# POWER.net
KiCad netlist of a schematic drawn in Altium Designer
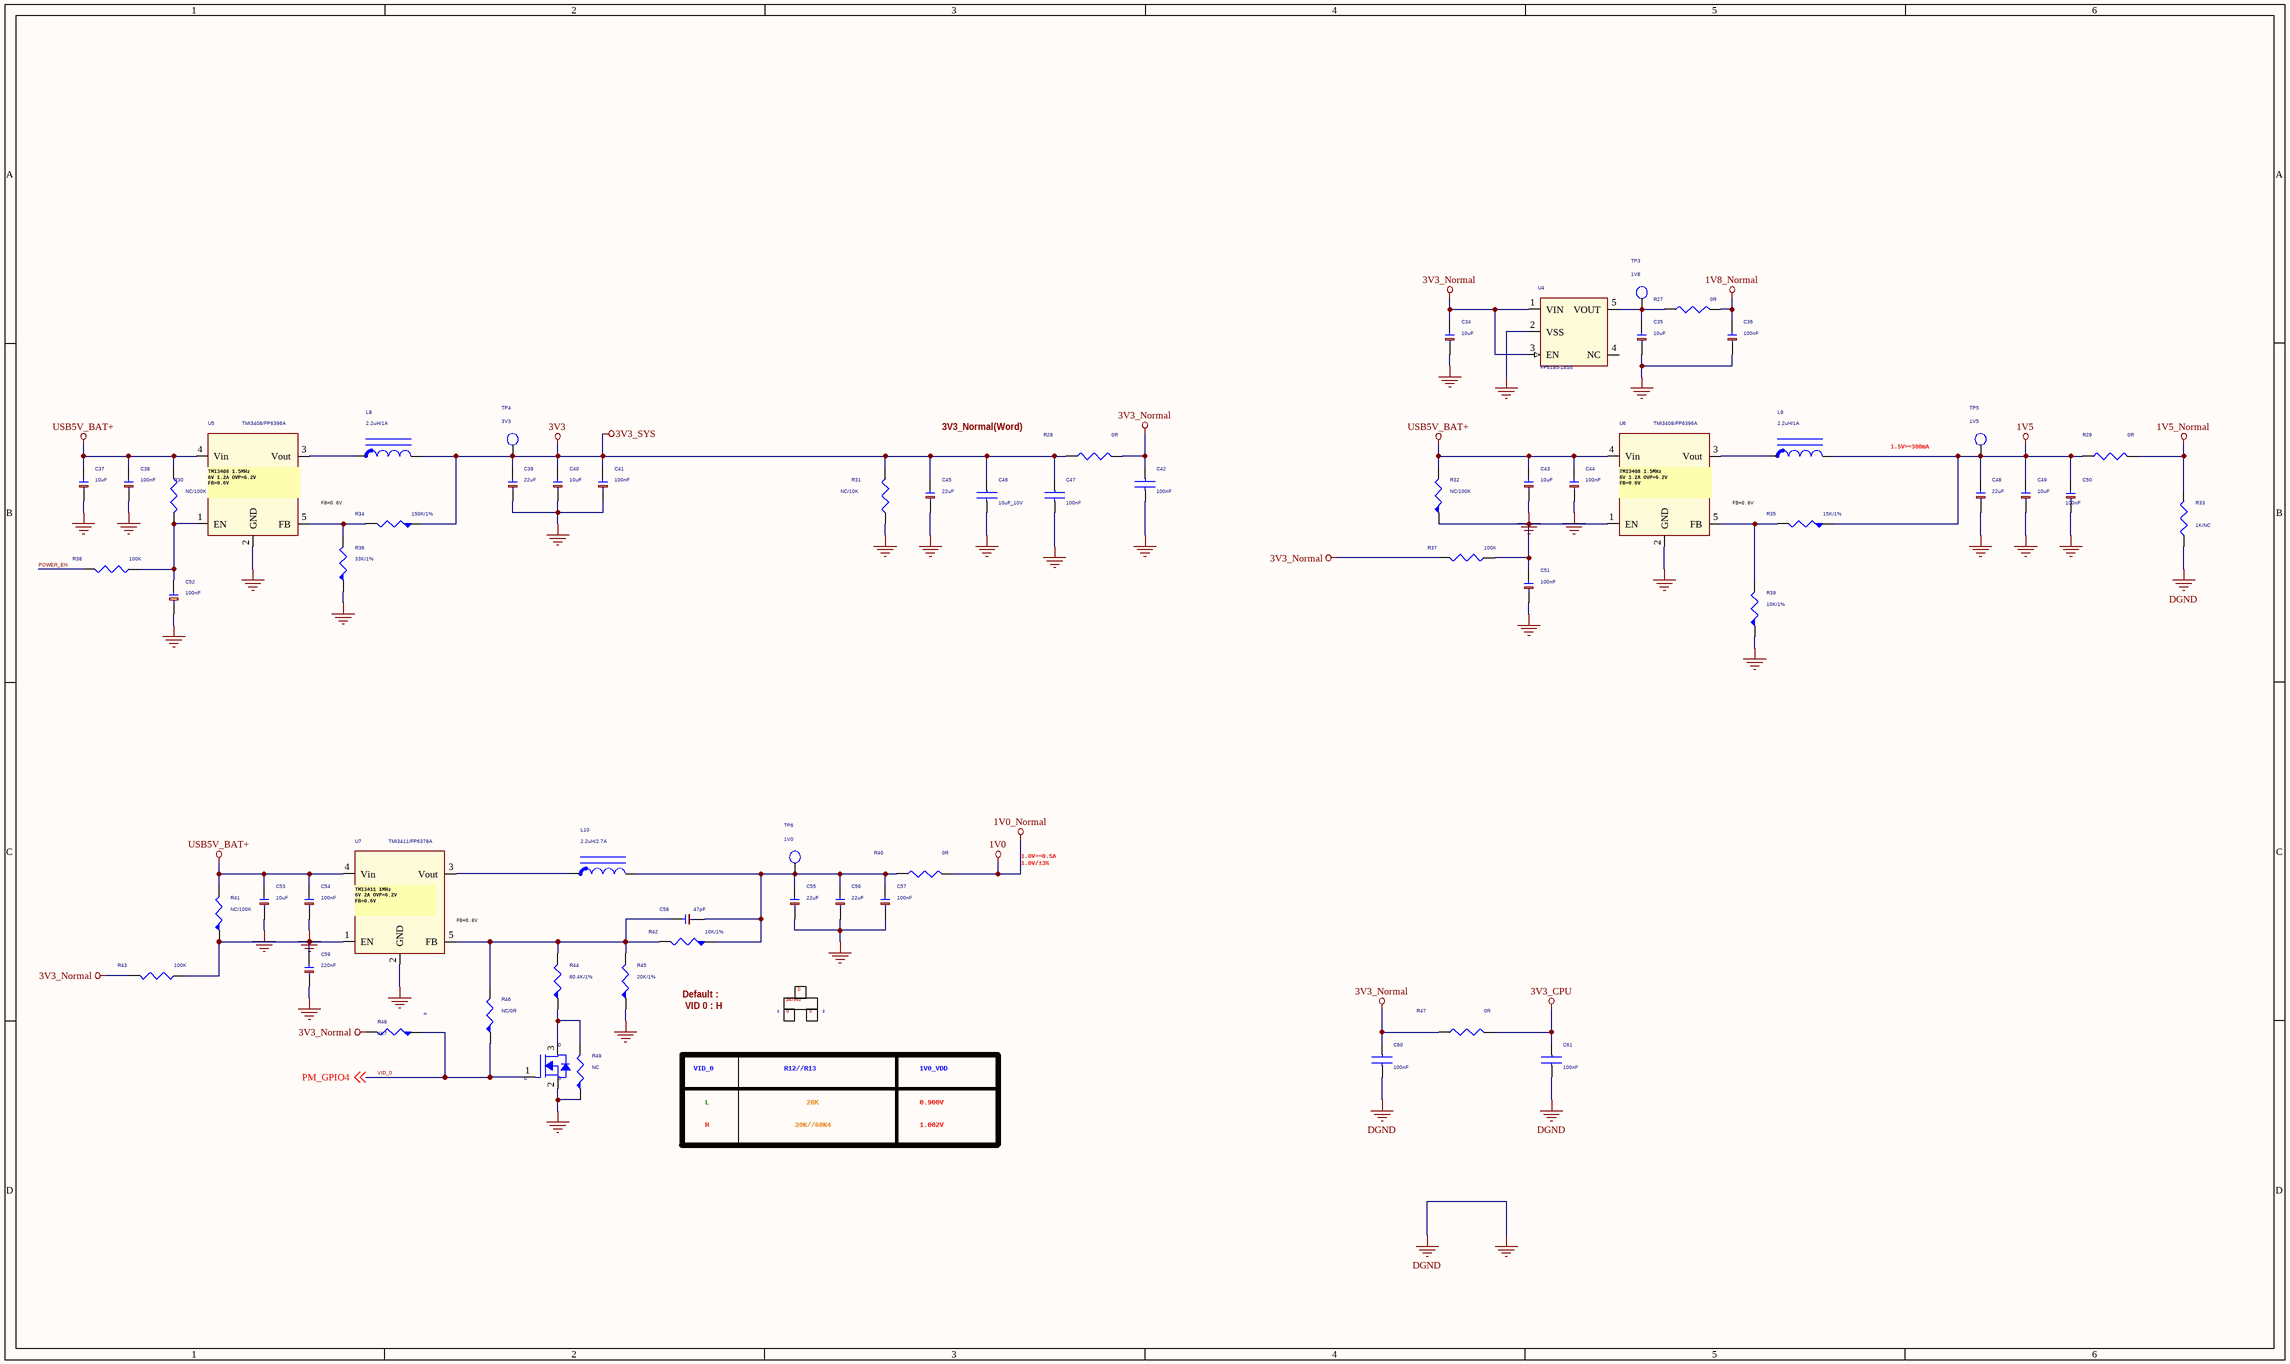
[diagram p0: POWER.SchDoc]

(export (version "E")
  (design (tool "Eeschema 10.0.6"))
  (components
    (comp (ref "C34")
      (value "10uF")
      (footprint "C0402")
      (description "[ 100nF(0.1uF),10V,X7R ](0402)")
      (fields (field (name "CREATOR") "Alan.Liu#6135/0920796617"))
      (libsource (lib "*") (part "C0402/100nF/10V/X7R"))
    )
    (comp (ref "C35")
      (value "10uF")
      (footprint "C0402")
      (description "[ 100nF(0.1uF),10V,X7R ](0402)")
      (fields (field (name "CREATOR") "Alan.Liu#6135/0920796617"))
      (libsource (lib "*") (part "C0402/100nF/10V/X7R"))
    )
    (comp (ref "C36")
      (value "100nF")
      (footprint "C0402")
      (description "[ 100nF(0.1uF),10V,X7R ](0402)")
      (fields (field (name "CREATOR") "Alan.Liu#6135/0920796617"))
      (libsource (lib "*") (part "C0402/100nF/10V/X7R"))
    )
    (comp (ref "C37")
      (value "10uF")
      (footprint "C0402")
      (description "[ 100nF(0.1uF),10V,X7R ](0402)")
      (fields (field (name "CREATOR") "Alan.Liu#6135/0920796617"))
      (libsource (lib "*") (part "C0402/100nF/10V/X7R"))
    )
    (comp (ref "C38")
      (value "100nF")
      (footprint "C0402")
      (description "[ 100nF(0.1uF),10V,X7R ](0402)")
      (fields (field (name "CREATOR") "Alan.Liu#6135/0920796617"))
      (libsource (lib "*") (part "C0402/100nF/10V/X7R"))
    )
    (comp (ref "C39")
      (value "22uF")
      (footprint "C0402")
      (description "[ 100nF(0.1uF),10V,X7R ](0402)")
      (fields (field (name "CREATOR") "Alan.Liu#6135/0920796617"))
      (libsource (lib "*") (part "C0402/100nF/10V/X7R"))
    )
    (comp (ref "C40")
      (value "10uF")
      (footprint "C0402")
      (description "[ 100nF(0.1uF),10V,X7R ](0402)")
      (fields (field (name "CREATOR") "Alan.Liu#6135/0920796617"))
      (libsource (lib "*") (part "C0402/100nF/10V/X7R"))
    )
    (comp (ref "C41")
      (value "100nF")
      (footprint "C0402")
      (description "[ 100nF(0.1uF),10V,X7R ](0402)")
      (fields (field (name "CREATOR") "Alan.Liu#6135/0920796617"))
      (libsource (lib "*") (part "C0402/100nF/10V/X7R"))
    )
    (comp (ref "C42") (value "100nF") (footprint "C0402") (libsource (lib "*") (part "CAP NP2")))
    (comp (ref "C43")
      (value "10uF")
      (footprint "C0402")
      (description "[ 100nF(0.1uF),10V,X7R ](0402)")
      (fields (field (name "CREATOR") "Alan.Liu#6135/0920796617"))
      (libsource (lib "*") (part "C0402/100nF/10V/X7R"))
    )
    (comp (ref "C44")
      (value "100nF")
      (footprint "C0402")
      (description "[ 100nF(0.1uF),10V,X7R ](0402)")
      (fields (field (name "CREATOR") "Alan.Liu#6135/0920796617"))
      (libsource (lib "*") (part "C0402/100nF/10V/X7R"))
    )
    (comp (ref "C45")
      (value "22uF")
      (footprint "C0402")
      (description "[ 100nF(0.1uF),10V,X7R ](0402)")
      (fields (field (name "CREATOR") "Alan.Liu#6135/0920796617"))
      (libsource (lib "*") (part "C0402/100nF/10V/X7R"))
    )
    (comp (ref "C46") (value "10uF_10V") (footprint "C0603") (libsource (lib "*") (part "CAP NP2")))
    (comp (ref "C47") (value "100nF") (footprint "C0402") (libsource (lib "*") (part "CAP NP2")))
    (comp (ref "C48")
      (value "22uF")
      (footprint "C0402")
      (description "[ 100nF(0.1uF),10V,X7R ](0402)")
      (fields (field (name "CREATOR") "Alan.Liu#6135/0920796617"))
      (libsource (lib "*") (part "C0402/100nF/10V/X7R"))
    )
    (comp (ref "C49")
      (value "10uF")
      (footprint "C0402")
      (description "[ 100nF(0.1uF),10V,X7R ](0402)")
      (fields (field (name "CREATOR") "Alan.Liu#6135/0920796617"))
      (libsource (lib "*") (part "C0402/100nF/10V/X7R"))
    )
    (comp (ref "C50") (value "100nF") (footprint "C0402") (libsource (lib "*") (part "C0805_10uF")))
    (comp (ref "C51")
      (value "100nF")
      (footprint "C0402")
      (description "[ 100nF(0.1uF),10V,X7R ](0402)")
      (fields (field (name "CREATOR") "Alan.Liu#6135/0920796617"))
      (libsource (lib "*") (part "C0402/100nF/10V/X7R"))
    )
    (comp (ref "C52")
      (value "100nF")
      (footprint "C0402")
      (description "[ 100nF(0.1uF),10V,X7R ](0402)")
      (fields (field (name "CREATOR") "Alan.Liu#6135/0920796617"))
      (libsource (lib "*") (part "C0402/100nF/10V/X7R"))
    )
    (comp (ref "C53")
      (value "10uF")
      (footprint "C0402")
      (description "[ 100nF(0.1uF),10V,X7R ](0402)")
      (fields (field (name "CREATOR") "Alan.Liu#6135/0920796617"))
      (libsource (lib "*") (part "C0402/100nF/10V/X7R"))
    )
    (comp (ref "C54")
      (value "100nF")
      (footprint "C0402")
      (description "[ 100nF(0.1uF),10V,X7R ](0402)")
      (fields (field (name "CREATOR") "Alan.Liu#6135/0920796617"))
      (libsource (lib "*") (part "C0402/100nF/10V/X7R"))
    )
    (comp (ref "C55")
      (value "22uF")
      (footprint "C0402")
      (description "[ 100nF(0.1uF),10V,X7R ](0402)")
      (fields (field (name "CREATOR") "Alan.Liu#6135/0920796617"))
      (libsource (lib "*") (part "C0402/100nF/10V/X7R"))
    )
    (comp (ref "C56")
      (value "22uF")
      (footprint "C0402")
      (description "[ 100nF(0.1uF),10V,X7R ](0402)")
      (fields (field (name "CREATOR") "Alan.Liu#6135/0920796617"))
      (libsource (lib "*") (part "C0402/100nF/10V/X7R"))
    )
    (comp (ref "C57")
      (value "100nF")
      (footprint "C0402")
      (description "[ 100nF(0.1uF),10V,X7R ](0402)")
      (fields (field (name "CREATOR") "Alan.Liu#6135/0920796617"))
      (libsource (lib "*") (part "C0402/100nF/10V/X7R"))
    )
    (comp (ref "C58")
      (value "47pF")
      (footprint "C0402")
      (description "[ 100nF(0.1uF),10V,X7R ](0402)")
      (fields (field (name "CREATOR") "Alan.Liu#6135/0920796617"))
      (libsource (lib "") (part "C0402/100nF/10V/X7R_1"))
    )
    (comp (ref "C59")
      (value "220nF")
      (footprint "C0402")
      (description "[ 100nF(0.1uF),10V,X7R ](0402)")
      (fields (field (name "CREATOR") "Alan.Liu#6135/0920796617"))
      (libsource (lib "*") (part "C0402/100nF/10V/X7R"))
    )
    (comp (ref "C60") (value "100nF") (footprint "C0402") (libsource (lib "*") (part "CAP NP2")))
    (comp (ref "C61") (value "100nF") (footprint "C0402") (libsource (lib "*") (part "CAP NP2")))
    (comp (ref "L8")
      (value "2.2uH/1A")
      (footprint "SWPA3015S")
      (fields (field (name "CREATOR") "Alan.Liu#6135/0920796617"))
      (libsource (lib "*") (part "CHOKE_4.7uH/4.1A-L8.0W8.0H4.0"))
    )
    (comp (ref "L9")
      (value "2.2uH/1A")
      (footprint "SWPA3015S")
      (fields (field (name "CREATOR") "Alan.Liu#6135/0920796617"))
      (libsource (lib "*") (part "CHOKE_4.7uH/4.1A-L8.0W8.0H4.0"))
    )
    (comp (ref "L10")
      (value "2.2uH/2.7A")
      (footprint "L-MLPS-4018")
      (fields (field (name "CREATOR") "Alan.Liu#6135/0920796617"))
      (libsource (lib "*") (part "CHOKE_4.7uH/4.1A-L8.0W8.0H4.0"))
    )
    (comp (ref "Q4") (value "2N7002") (footprint "SOT-23") (libsource (lib "*") (part "AO3400_SOT23")))
    (comp (ref "R27") (value "0R") (footprint "R0402") (libsource (lib "*") (part "R_Dup1")))
    (comp (ref "R28") (value "0R") (footprint "R1210") (libsource (lib "*") (part "R_Dup2")))
    (comp (ref "R29") (value "0R") (footprint "R1210") (libsource (lib "*") (part "R_Dup2")))
    (comp (ref "R30") (value "NC/100K") (footprint "R0402") (libsource (lib "*") (part "R_Dup2")))
    (comp (ref "R31") (value "NC/10K") (footprint "R0402") (libsource (lib "*") (part "R_Dup2")))
    (comp (ref "R32") (value "NC/100K") (footprint "R0402") (libsource (lib "*") (part "R-PIN-Mark")))
    (comp (ref "R33") (value "1K/NC") (footprint "R0402") (libsource (lib "*") (part "R_Dup2")))
    (comp (ref "R34") (value "150K/1%") (footprint "R0402") (libsource (lib "*") (part "R-PIN-Mark")))
    (comp (ref "R35") (value "15K/1%") (footprint "R0402") (libsource (lib "*") (part "R-PIN-Mark")))
    (comp (ref "R36") (value "33K/1%") (footprint "R0402") (libsource (lib "*") (part "R-PIN-Mark")))
    (comp (ref "R37") (value "100K") (footprint "R0402") (libsource (lib "*") (part "R_Dup2")))
    (comp (ref "R38") (value "100K") (footprint "R0402") (libsource (lib "*") (part "R_Dup2")))
    (comp (ref "R39") (value "10K/1%") (footprint "R0402") (libsource (lib "*") (part "R-PIN-Mark")))
    (comp (ref "R40") (value "0R") (footprint "R1210") (libsource (lib "*") (part "R_Dup2")))
    (comp (ref "R41") (value "NC/100K") (footprint "R0402") (libsource (lib "*") (part "R-PIN-Mark")))
    (comp (ref "R42") (value "10K/1%") (footprint "R0402") (libsource (lib "*") (part "R-PIN-Mark")))
    (comp (ref "R43") (value "100K") (footprint "R0402") (libsource (lib "*") (part "R_Dup2")))
    (comp (ref "R44") (value "60.4K/1%") (footprint "R0402") (libsource (lib "*") (part "R-PIN-Mark")))
    (comp (ref "R45") (value "20K/1%") (footprint "R0402") (libsource (lib "*") (part "R-PIN-Mark")))
    (comp (ref "R46") (value "NC/0R") (footprint "R0402") (libsource (lib "*") (part "R-PIN-Mark")))
    (comp (ref "R47") (value "0R") (footprint "R1210") (libsource (lib "*") (part "R_Dup2")))
    (comp (ref "R48") (value "4K7") (footprint "R0402") (libsource (lib "*") (part "R-PIN-Mark")))
    (comp (ref "R49") (value "NC") (footprint "R0402") (libsource (lib "*") (part "R-PIN-Mark")))
    (comp (ref "TP3") (value "1V8") (footprint "TP") (libsource (lib "*") (part "T POINT R")))
    (comp (ref "TP4") (value "3V3") (footprint "TP") (libsource (lib "*") (part "T POINT R")))
    (comp (ref "TP5") (value "1V5") (footprint "TP") (libsource (lib "*") (part "T POINT R")))
    (comp (ref "TP6") (value "1V0") (footprint "TP") (libsource (lib "*") (part "T POINT R")))
    (comp (ref "U4") (value "FP6185-18S5") (footprint "SOT23-5P") (libsource (lib "*") (part "ADP1610_7")))
    (comp (ref "U5")
      (value "TMI3408/FP6396A")
      (footprint "SOT-23-5")
      (description "iD9306-AD")
      (fields (field (name "PART NUMBER") "300035100G"))
      (libsource (lib "*") (part "LDO,iD9306-AD,300mA_3"))
    )
    (comp (ref "U6")
      (value "TMI3408/FP6396A")
      (footprint "SOT-23-5")
      (description "iD9306-AD")
      (fields (field (name "PART NUMBER") "300035100G"))
      (libsource (lib "*") (part "LDO,iD9306-AD,300mA_3"))
    )
    (comp (ref "U7")
      (value "TMI3411/FP6378A")
      (footprint "SOT-23-5")
      (description "iD9306-AD")
      (fields (field (name "PART NUMBER") "300035100G"))
      (libsource (lib "*") (part "LDO,iD9306-AD,300mA_4"))
    )
  )
  (nets
    (net (code "1") (name "/POWER_EN") (class "Default")
      (node (ref "R38") (pin "2") (pinfunction "2_2") (pintype "passive"))
    )
    (net (code "2") (name "1V0") (class "Default")
      (node (ref "R40") (pin "2") (pinfunction "2_2") (pintype "passive"))
    )
    (net (code "3") (name "1V5") (class "Default")
      (node (ref "C48") (pin "2") (pinfunction "2_2") (pintype "passive"))
      (node (ref "C49") (pin "2") (pinfunction "2_2") (pintype "passive"))
      (node (ref "C50") (pin "1") (pinfunction "1_1") (pintype "passive"))
      (node (ref "L9") (pin "2") (pinfunction "2_2") (pintype "passive"))
      (node (ref "R29") (pin "1") (pinfunction "1_1") (pintype "passive"))
      (node (ref "R35") (pin "1") (pinfunction "1_1") (pintype "passive"))
      (node (ref "TP5") (pin "1") (pinfunction "TP_1") (pintype "passive"))
    )
    (net (code "4") (name "1V5_Normal") (class "Default")
      (node (ref "R29") (pin "2") (pinfunction "2_2") (pintype "passive"))
      (node (ref "R33") (pin "1") (pinfunction "1_1") (pintype "passive"))
    )
    (net (code "5") (name "1V8_Normal") (class "Default")
      (node (ref "C36") (pin "2") (pinfunction "2_2") (pintype "passive"))
      (node (ref "R27") (pin "2") (pinfunction "2_2") (pintype "passive"))
    )
    (net (code "6") (name "3V3") (class "Default")
      (node (ref "C39") (pin "2") (pinfunction "2_2") (pintype "passive"))
      (node (ref "C40") (pin "2") (pinfunction "2_2") (pintype "passive"))
      (node (ref "C41") (pin "2") (pinfunction "2_2") (pintype "passive"))
      (node (ref "C45") (pin "2") (pinfunction "2_2") (pintype "passive"))
      (node (ref "C46") (pin "1") (pinfunction "1_1") (pintype "passive"))
      (node (ref "C47") (pin "1") (pinfunction "1_1") (pintype "passive"))
      (node (ref "L8") (pin "2") (pinfunction "2_2") (pintype "passive"))
      (node (ref "R28") (pin "1") (pinfunction "1_1") (pintype "passive"))
      (node (ref "R31") (pin "1") (pinfunction "1_1") (pintype "passive"))
      (node (ref "R34") (pin "1") (pinfunction "1_1") (pintype "passive"))
      (node (ref "TP4") (pin "1") (pinfunction "TP_1") (pintype "passive"))
    )
    (net (code "7") (name "3V3_CPU") (class "Default")
      (node (ref "C61") (pin "1") (pinfunction "1_1") (pintype "passive"))
      (node (ref "R47") (pin "2") (pinfunction "2_2") (pintype "passive"))
    )
    (net (code "8") (name "3V3_Normal") (class "Default")
      (node (ref "C34") (pin "2") (pinfunction "2_2") (pintype "passive"))
      (node (ref "C42") (pin "1") (pinfunction "1_1") (pintype "passive"))
      (node (ref "C60") (pin "1") (pinfunction "1_1") (pintype "passive"))
      (node (ref "R28") (pin "2") (pinfunction "2_2") (pintype "passive"))
      (node (ref "R37") (pin "2") (pinfunction "2_2") (pintype "passive"))
      (node (ref "R43") (pin "1") (pinfunction "1_1") (pintype "passive"))
      (node (ref "R47") (pin "1") (pinfunction "1_1") (pintype "passive"))
      (node (ref "R48") (pin "2") (pinfunction "2_2") (pintype "passive"))
      (node (ref "U4") (pin "1") (pinfunction "VIN_1") (pintype "power_in"))
      (node (ref "U4") (pin "3") (pinfunction "EN_3") (pintype "input"))
    )
    (net (code "9") (name "DGND") (class "Default")
      (node (ref "C34") (pin "1") (pinfunction "1_1") (pintype "passive"))
      (node (ref "C35") (pin "1") (pinfunction "1_1") (pintype "passive"))
      (node (ref "C36") (pin "1") (pinfunction "1_1") (pintype "passive"))
      (node (ref "C37") (pin "1") (pinfunction "1_1") (pintype "passive"))
      (node (ref "C38") (pin "1") (pinfunction "1_1") (pintype "passive"))
      (node (ref "C39") (pin "1") (pinfunction "1_1") (pintype "passive"))
      (node (ref "C40") (pin "1") (pinfunction "1_1") (pintype "passive"))
      (node (ref "C41") (pin "1") (pinfunction "1_1") (pintype "passive"))
      (node (ref "C42") (pin "2") (pinfunction "2_2") (pintype "passive"))
      (node (ref "C43") (pin "1") (pinfunction "1_1") (pintype "passive"))
      (node (ref "C44") (pin "1") (pinfunction "1_1") (pintype "passive"))
      (node (ref "C45") (pin "1") (pinfunction "1_1") (pintype "passive"))
      (node (ref "C46") (pin "2") (pinfunction "2_2") (pintype "passive"))
      (node (ref "C47") (pin "2") (pinfunction "2_2") (pintype "passive"))
      (node (ref "C48") (pin "1") (pinfunction "1_1") (pintype "passive"))
      (node (ref "C49") (pin "1") (pinfunction "1_1") (pintype "passive"))
      (node (ref "C50") (pin "2") (pinfunction "2_2") (pintype "passive"))
      (node (ref "C51") (pin "1") (pinfunction "1_1") (pintype "passive"))
      (node (ref "C52") (pin "1") (pinfunction "1_1") (pintype "passive"))
      (node (ref "C53") (pin "1") (pinfunction "1_1") (pintype "passive"))
      (node (ref "C54") (pin "1") (pinfunction "1_1") (pintype "passive"))
      (node (ref "C55") (pin "1") (pinfunction "1_1") (pintype "passive"))
      (node (ref "C56") (pin "1") (pinfunction "1_1") (pintype "passive"))
      (node (ref "C57") (pin "1") (pinfunction "1_1") (pintype "passive"))
      (node (ref "C59") (pin "1") (pinfunction "1_1") (pintype "passive"))
      (node (ref "C60") (pin "2") (pinfunction "2_2") (pintype "passive"))
      (node (ref "C61") (pin "2") (pinfunction "2_2") (pintype "passive"))
      (node (ref "Q4") (pin "2") (pinfunction "SOURCE_2") (pintype "passive"))
      (node (ref "R31") (pin "2") (pinfunction "2_2") (pintype "passive"))
      (node (ref "R33") (pin "2") (pinfunction "2_2") (pintype "passive"))
      (node (ref "R36") (pin "1") (pinfunction "1_1") (pintype "passive"))
      (node (ref "R39") (pin "1") (pinfunction "1_1") (pintype "passive"))
      (node (ref "R45") (pin "1") (pinfunction "1_1") (pintype "passive"))
      (node (ref "R49") (pin "1") (pinfunction "1_1") (pintype "passive"))
      (node (ref "U4") (pin "2") (pinfunction "VSS_2") (pintype "power_in"))
      (node (ref "U5") (pin "2") (pinfunction "GND_2") (pintype "passive"))
      (node (ref "U6") (pin "2") (pinfunction "GND_2") (pintype "passive"))
      (node (ref "U7") (pin "2") (pinfunction "GND_2") (pintype "passive"))
    )
    (net (code "10") (name "Net-(Q4-DRAIN)") (class "Default")
      (node (ref "Q4") (pin "3") (pinfunction "DRAIN_3") (pintype "passive"))
      (node (ref "R44") (pin "1") (pinfunction "1_1") (pintype "passive"))
      (node (ref "R49") (pin "2") (pinfunction "2_2") (pintype "passive"))
    )
    (net (code "11") (name "Net-(TP3-TP)") (class "Default")
      (node (ref "C35") (pin "2") (pinfunction "2_2") (pintype "passive"))
      (node (ref "R27") (pin "1") (pinfunction "1_1") (pintype "passive"))
      (node (ref "TP3") (pin "1") (pinfunction "TP_1") (pintype "passive"))
      (node (ref "U4") (pin "5") (pinfunction "VOUT_5") (pintype "power_in"))
    )
    (net (code "12") (name "Net-(TP6-TP)") (class "Default")
      (node (ref "C55") (pin "2") (pinfunction "2_2") (pintype "passive"))
      (node (ref "C56") (pin "2") (pinfunction "2_2") (pintype "passive"))
      (node (ref "C57") (pin "2") (pinfunction "2_2") (pintype "passive"))
      (node (ref "C58") (pin "1") (pinfunction "1_1") (pintype "passive"))
      (node (ref "L10") (pin "2") (pinfunction "2_2") (pintype "passive"))
      (node (ref "R40") (pin "1") (pinfunction "1_1") (pintype "passive"))
      (node (ref "R42") (pin "1") (pinfunction "1_1") (pintype "passive"))
      (node (ref "TP6") (pin "1") (pinfunction "TP_1") (pintype "passive"))
    )
    (net (code "13") (name "Net-(U5-EN)") (class "Default")
      (node (ref "C52") (pin "2") (pinfunction "2_2") (pintype "passive"))
      (node (ref "R30") (pin "1") (pinfunction "1_1") (pintype "passive"))
      (node (ref "R38") (pin "1") (pinfunction "1_1") (pintype "passive"))
      (node (ref "U5") (pin "1") (pinfunction "EN_1") (pintype "passive"))
    )
    (net (code "14") (name "Net-(U5-FB)") (class "Default")
      (node (ref "R34") (pin "2") (pinfunction "2_2") (pintype "passive"))
      (node (ref "R36") (pin "2") (pinfunction "2_2") (pintype "passive"))
      (node (ref "U5") (pin "5") (pinfunction "FB_5") (pintype "passive"))
    )
    (net (code "15") (name "Net-(U5-Vout)") (class "Default")
      (node (ref "L8") (pin "1") (pinfunction "1_1") (pintype "passive"))
      (node (ref "U5") (pin "3") (pinfunction "Vout_3") (pintype "passive"))
    )
    (net (code "16") (name "Net-(U6-EN)") (class "Default")
      (node (ref "C51") (pin "2") (pinfunction "2_2") (pintype "passive"))
      (node (ref "R32") (pin "1") (pinfunction "1_1") (pintype "passive"))
      (node (ref "R37") (pin "1") (pinfunction "1_1") (pintype "passive"))
      (node (ref "U6") (pin "1") (pinfunction "EN_1") (pintype "passive"))
    )
    (net (code "17") (name "Net-(U6-FB)") (class "Default")
      (node (ref "R35") (pin "2") (pinfunction "2_2") (pintype "passive"))
      (node (ref "R39") (pin "2") (pinfunction "2_2") (pintype "passive"))
      (node (ref "U6") (pin "5") (pinfunction "FB_5") (pintype "passive"))
    )
    (net (code "18") (name "Net-(U6-Vout)") (class "Default")
      (node (ref "L9") (pin "1") (pinfunction "1_1") (pintype "passive"))
      (node (ref "U6") (pin "3") (pinfunction "Vout_3") (pintype "passive"))
    )
    (net (code "19") (name "Net-(U7-EN)") (class "Default")
      (node (ref "C59") (pin "2") (pinfunction "2_2") (pintype "passive"))
      (node (ref "R41") (pin "1") (pinfunction "1_1") (pintype "passive"))
      (node (ref "R43") (pin "2") (pinfunction "2_2") (pintype "passive"))
      (node (ref "U7") (pin "1") (pinfunction "EN_1") (pintype "passive"))
    )
    (net (code "20") (name "Net-(U7-FB)") (class "Default")
      (node (ref "C58") (pin "2") (pinfunction "2_2") (pintype "passive"))
      (node (ref "R42") (pin "2") (pinfunction "2_2") (pintype "passive"))
      (node (ref "R44") (pin "2") (pinfunction "2_2") (pintype "passive"))
      (node (ref "R45") (pin "2") (pinfunction "2_2") (pintype "passive"))
      (node (ref "R46") (pin "2") (pinfunction "2_2") (pintype "passive"))
      (node (ref "U7") (pin "5") (pinfunction "FB_5") (pintype "passive"))
    )
    (net (code "21") (name "Net-(U7-Vout)") (class "Default")
      (node (ref "L10") (pin "1") (pinfunction "1_1") (pintype "passive"))
      (node (ref "U7") (pin "3") (pinfunction "Vout_3") (pintype "passive"))
    )
    (net (code "22") (name "PM_GPIO4") (class "Default")
      (node (ref "Q4") (pin "1") (pinfunction "GATE_1") (pintype "passive"))
      (node (ref "R46") (pin "1") (pinfunction "1_1") (pintype "passive"))
      (node (ref "R48") (pin "1") (pinfunction "1_1") (pintype "passive"))
    )
    (net (code "23") (name "USB5V_BAT+") (class "Default")
      (node (ref "C37") (pin "2") (pinfunction "2_2") (pintype "passive"))
      (node (ref "C38") (pin "2") (pinfunction "2_2") (pintype "passive"))
      (node (ref "C43") (pin "2") (pinfunction "2_2") (pintype "passive"))
      (node (ref "C44") (pin "2") (pinfunction "2_2") (pintype "passive"))
      (node (ref "C53") (pin "2") (pinfunction "2_2") (pintype "passive"))
      (node (ref "C54") (pin "2") (pinfunction "2_2") (pintype "passive"))
      (node (ref "R30") (pin "2") (pinfunction "2_2") (pintype "passive"))
      (node (ref "R32") (pin "2") (pinfunction "2_2") (pintype "passive"))
      (node (ref "R41") (pin "2") (pinfunction "2_2") (pintype "passive"))
      (node (ref "U5") (pin "4") (pinfunction "Vin_4") (pintype "passive"))
      (node (ref "U6") (pin "4") (pinfunction "Vin_4") (pintype "passive"))
      (node (ref "U7") (pin "4") (pinfunction "Vin_4") (pintype "passive"))
    )
    (net (code "24") (name "unconnected-(U4-NC-Pad4)") (class "Default")
      (node (ref "U4") (pin "4") (pinfunction "NC_4") (pintype "passive"))
    )
  )
)
